# Escorna_Shield_botoneira_2_0B.net
KiCad netlist of a schematic drawn in EAGLE
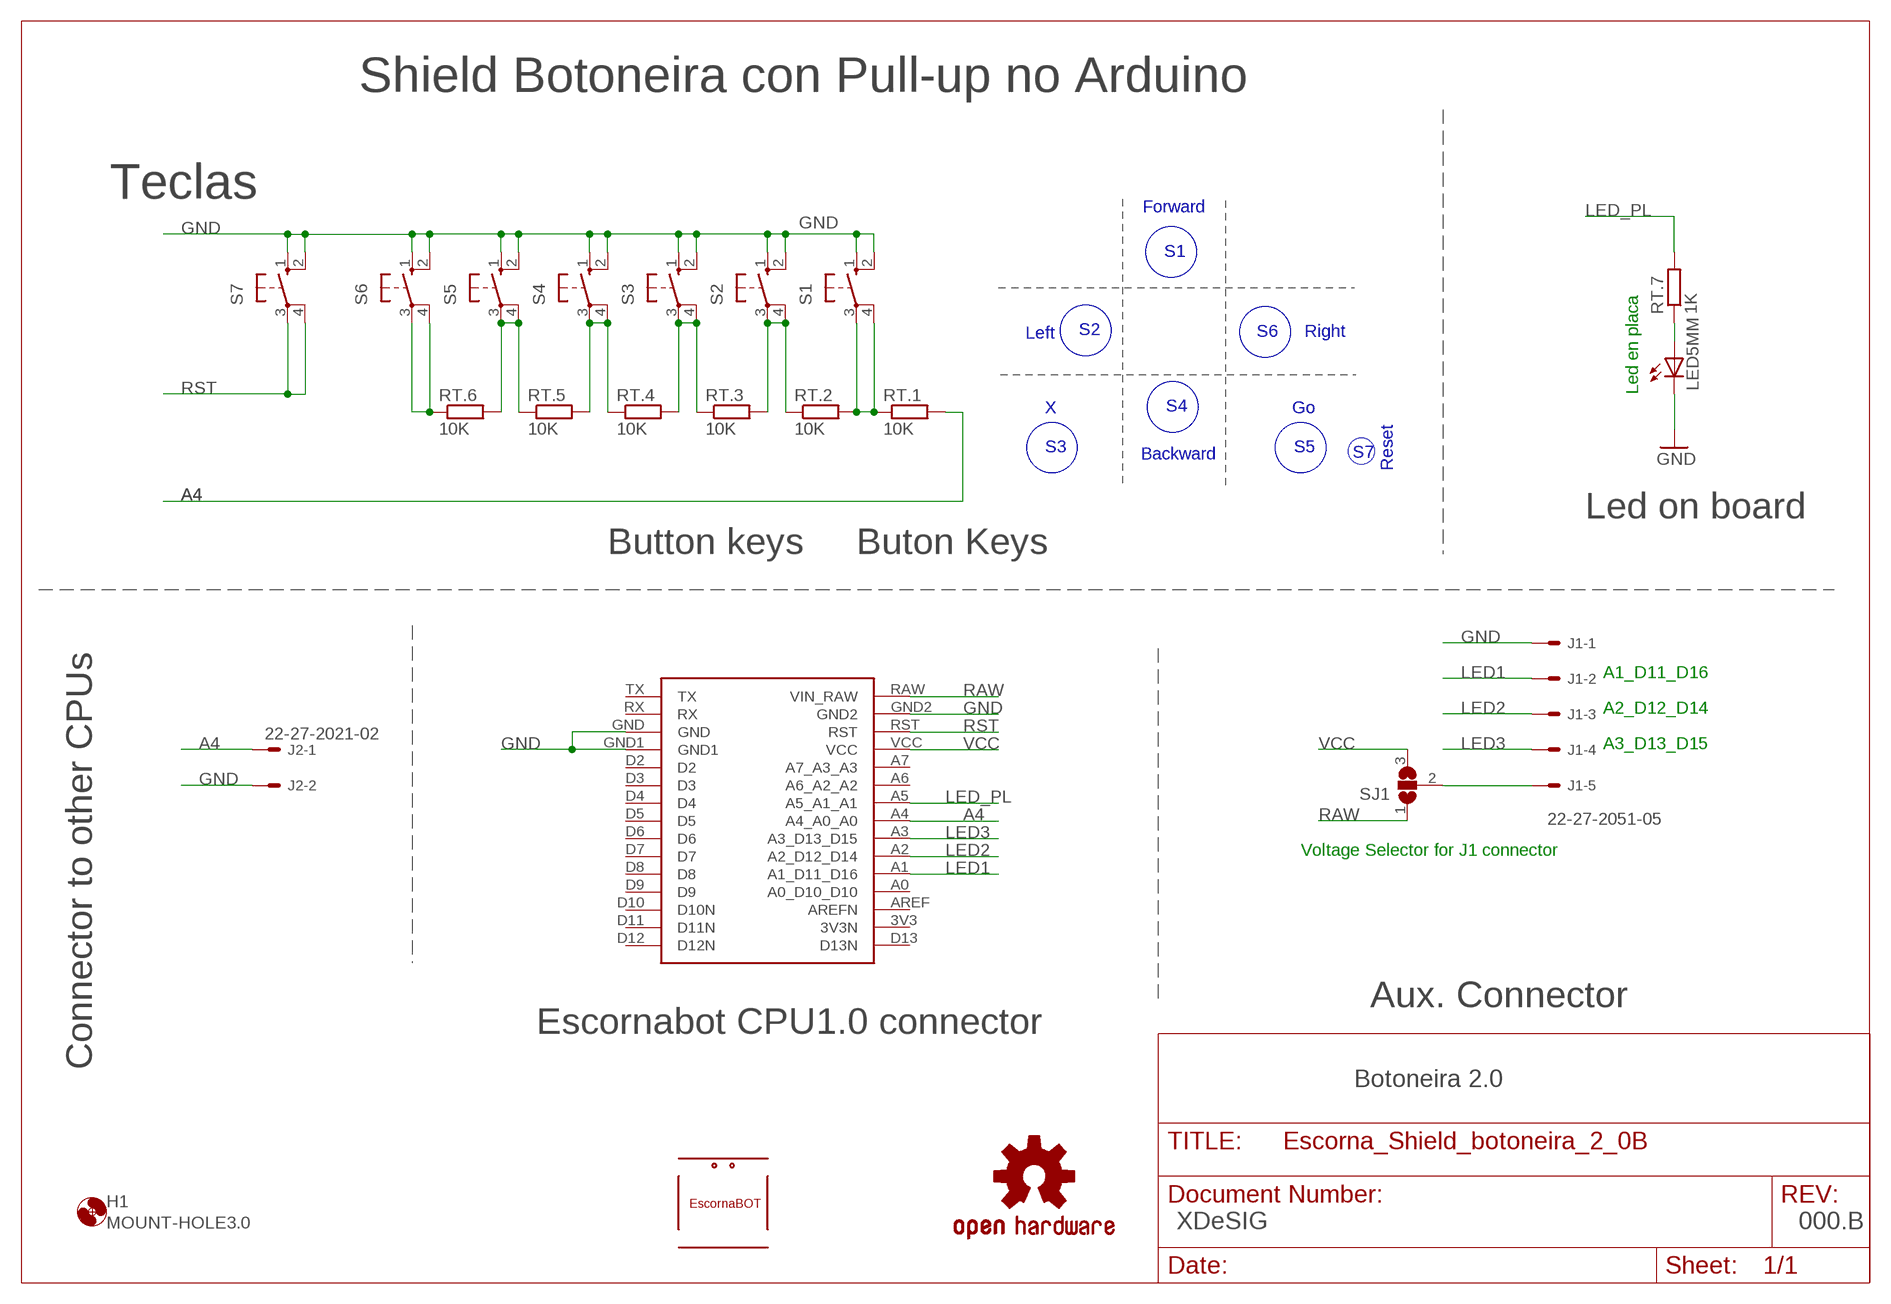
[diagram p0: schematic, sheet 1]

(export (version "E")
  (design (tool "Eeschema 10.0.6"))
  (components
    (comp (ref "ESSH1")
      (value "OUTL_ESCORNASHILED")
      (footprint "eagle-import:OUTL_ESCORNASHIELD")
      (libsource (lib "eagle-import") (part "OUTL_ESCORNASHILED"))
    )
    (comp (ref "H1")
      (value "MOUNT-HOLE3.0")
      (footprint "eagle-import:3,0")
      (libsource (lib "eagle-import") (part "MOUNT-HOLE3.0"))
    )
    (comp (ref "J1")
      (value "22-27-2051-05")
      (footprint "eagle-import:6410-05")
      (libsource (lib "eagle-import") (part "22-?-0527-2051"))
    )
    (comp (ref "J2")
      (value "22-27-2021-02")
      (footprint "eagle-import:6410-02")
      (libsource (lib "eagle-import") (part "22-?-0227-2021"))
    )
    (comp (ref "LED5MM")
      (value "LED5MM")
      (footprint "eagle-import:LED5MM")
      (libsource (lib "eagle-import") (part "LED5MM"))
    )
    (comp (ref "LOGO2")
      (value "OSHW-LOGOS")
      (footprint "eagle-import:OSHW-LOGO-S")
      (libsource (lib "eagle-import") (part "OSHW-LOGOS"))
    )
    (comp (ref "RT.1")
      (value "10K")
      (footprint "eagle-import:0204_7")
      (libsource (lib "eagle-import") (part "R-EU_0204/7"))
    )
    (comp (ref "RT.2")
      (value "10K")
      (footprint "eagle-import:0204_7")
      (libsource (lib "eagle-import") (part "R-EU_0204/7"))
    )
    (comp (ref "RT.3")
      (value "10K")
      (footprint "eagle-import:0204_7")
      (libsource (lib "eagle-import") (part "R-EU_0204/7"))
    )
    (comp (ref "RT.4")
      (value "10K")
      (footprint "eagle-import:0204_7")
      (libsource (lib "eagle-import") (part "R-EU_0204/7"))
    )
    (comp (ref "RT.5")
      (value "10K")
      (footprint "eagle-import:0204_7")
      (libsource (lib "eagle-import") (part "R-EU_0204/7"))
    )
    (comp (ref "RT.6")
      (value "10K")
      (footprint "eagle-import:0204_7")
      (libsource (lib "eagle-import") (part "R-EU_0204/7"))
    )
    (comp (ref "RT.7")
      (value "1K")
      (footprint "eagle-import:0204_7")
      (libsource (lib "eagle-import") (part "R-EU_0204/7"))
    )
    (comp (ref "S1")
      (value "B3F-40XX")
      (footprint "eagle-import:B3F40XX_NH")
      (libsource (lib "eagle-import") (part "40-XX"))
    )
    (comp (ref "S2")
      (value "B3F-40XX")
      (footprint "eagle-import:B3F40XX_NH")
      (libsource (lib "eagle-import") (part "40-XX"))
    )
    (comp (ref "S3")
      (value "B3F-40XX")
      (footprint "eagle-import:B3F40XX_NH")
      (libsource (lib "eagle-import") (part "40-XX"))
    )
    (comp (ref "S4")
      (value "B3F-40XX")
      (footprint "eagle-import:B3F40XX_NH")
      (libsource (lib "eagle-import") (part "40-XX"))
    )
    (comp (ref "S5")
      (value "B3F-40XX")
      (footprint "eagle-import:B3F40XX_NH")
      (libsource (lib "eagle-import") (part "40-XX"))
    )
    (comp (ref "S6")
      (value "B3F-40XX")
      (footprint "eagle-import:B3F40XX_NH")
      (libsource (lib "eagle-import") (part "40-XX"))
    )
    (comp (ref "S7")
      (value "10-XX")
      (footprint "eagle-import:B3F-10XX")
      (fields (field (name "MPN") "B3F-1000"))
      (libsource (lib "eagle-import") (part "10-XX"))
    )
    (comp (ref "SJ1")
      (value "SOLDERJUMPER_2WAY")
      (footprint "eagle-import:SJ_2")
      (libsource (lib "eagle-import") (part "SOLDERJUMPER_2WAY"))
    )
    (comp (ref "U$1")
      (value "ESCORNABOT")
      (footprint "eagle-import:ESCORNA_PEQUE")
      (libsource (lib "eagle-import") (part "ESCORNABOT"))
    )
  )
  (nets
    (net (code "1") (name "/A4") (class "Default")
      (node (ref "ESSH1") (pin "A4") (pinfunction "A4_A0_A0_A4") (pintype "bidirectional"))
      (node (ref "J2") (pin "1") (pinfunction "S_1") (pintype "passive"))
      (node (ref "RT.1") (pin "2") (pinfunction "2_2") (pintype "passive"))
    )
    (net (code "2") (name "/LED1") (class "Default")
      (node (ref "ESSH1") (pin "A1") (pinfunction "A1_D11_D16_A1") (pintype "bidirectional"))
      (node (ref "J1") (pin "2") (pinfunction "S_2") (pintype "passive"))
    )
    (net (code "3") (name "/LED2") (class "Default")
      (node (ref "ESSH1") (pin "A2") (pinfunction "A2_D12_D14_A2") (pintype "bidirectional"))
      (node (ref "J1") (pin "3") (pinfunction "S_3") (pintype "passive"))
    )
    (net (code "4") (name "/LED3") (class "Default")
      (node (ref "ESSH1") (pin "A3") (pinfunction "A3_D13_D15_A3") (pintype "bidirectional"))
      (node (ref "J1") (pin "4") (pinfunction "S_4") (pintype "passive"))
    )
    (net (code "5") (name "/LED_PL") (class "Default")
      (node (ref "ESSH1") (pin "A5") (pinfunction "A5_A1_A1_A5") (pintype "bidirectional"))
      (node (ref "RT.7") (pin "2") (pinfunction "2_2") (pintype "passive"))
    )
    (net (code "6") (name "/RAW") (class "Default")
      (node (ref "ESSH1") (pin "RAW") (pinfunction "VIN_RAW_RAW") (pintype "bidirectional"))
      (node (ref "SJ1") (pin "1") (pinfunction "1_1") (pintype "passive"))
    )
    (net (code "7") (name "/RST") (class "Default")
      (node (ref "ESSH1") (pin "RST") (pinfunction "RST_RST") (pintype "bidirectional"))
      (node (ref "S7") (pin "3") (pinfunction "P_3") (pintype "passive"))
      (node (ref "S7") (pin "4") (pinfunction "P1_4") (pintype "passive"))
    )
    (net (code "8") (name "/VCC") (class "Default")
      (node (ref "ESSH1") (pin "VCC") (pinfunction "VCC_VCC") (pintype "bidirectional"))
      (node (ref "SJ1") (pin "3") (pinfunction "3_3") (pintype "passive"))
    )
    (net (code "9") (name "GND") (class "Default")
      (node (ref "ESSH1") (pin "GND") (pinfunction "GND_GND") (pintype "bidirectional"))
      (node (ref "ESSH1") (pin "GND1") (pinfunction "GND1_GND1") (pintype "bidirectional"))
      (node (ref "ESSH1") (pin "GND2") (pinfunction "GND2_GND2") (pintype "bidirectional"))
      (node (ref "J1") (pin "1") (pinfunction "S_1") (pintype "passive"))
      (node (ref "J2") (pin "2") (pinfunction "S_2") (pintype "passive"))
      (node (ref "LED5MM") (pin "K") (pinfunction "C_K") (pintype "passive"))
      (node (ref "S1") (pin "1") (pinfunction "S_1") (pintype "passive"))
      (node (ref "S1") (pin "2") (pinfunction "S1_2") (pintype "passive"))
      (node (ref "S2") (pin "1") (pinfunction "S_1") (pintype "passive"))
      (node (ref "S2") (pin "2") (pinfunction "S1_2") (pintype "passive"))
      (node (ref "S3") (pin "1") (pinfunction "S_1") (pintype "passive"))
      (node (ref "S3") (pin "2") (pinfunction "S1_2") (pintype "passive"))
      (node (ref "S4") (pin "1") (pinfunction "S_1") (pintype "passive"))
      (node (ref "S4") (pin "2") (pinfunction "S1_2") (pintype "passive"))
      (node (ref "S5") (pin "1") (pinfunction "S_1") (pintype "passive"))
      (node (ref "S5") (pin "2") (pinfunction "S1_2") (pintype "passive"))
      (node (ref "S6") (pin "1") (pinfunction "S_1") (pintype "passive"))
      (node (ref "S6") (pin "2") (pinfunction "S1_2") (pintype "passive"))
      (node (ref "S7") (pin "1") (pinfunction "S_1") (pintype "passive"))
      (node (ref "S7") (pin "2") (pinfunction "S1_2") (pintype "passive"))
    )
    (net (code "10") (name "Net-(J1E-S)") (class "Default")
      (node (ref "J1") (pin "5") (pinfunction "S_5") (pintype "passive"))
      (node (ref "SJ1") (pin "2") (pinfunction "2_2") (pintype "passive"))
    )
    (net (code "11") (name "Net-(LED5MM-PadA)") (class "Default")
      (node (ref "LED5MM") (pin "A") (pinfunction "A_A") (pintype "passive"))
      (node (ref "RT.7") (pin "1") (pinfunction "1_1") (pintype "passive"))
    )
    (net (code "12") (name "Net-(S1-P)") (class "Default")
      (node (ref "RT.1") (pin "1") (pinfunction "1_1") (pintype "passive"))
      (node (ref "RT.2") (pin "2") (pinfunction "2_2") (pintype "passive"))
      (node (ref "S1") (pin "3") (pinfunction "P_3") (pintype "passive"))
      (node (ref "S1") (pin "4") (pinfunction "P1_4") (pintype "passive"))
    )
    (net (code "13") (name "Net-(S2-P)") (class "Default")
      (node (ref "RT.2") (pin "1") (pinfunction "1_1") (pintype "passive"))
      (node (ref "RT.3") (pin "2") (pinfunction "2_2") (pintype "passive"))
      (node (ref "S2") (pin "3") (pinfunction "P_3") (pintype "passive"))
      (node (ref "S2") (pin "4") (pinfunction "P1_4") (pintype "passive"))
    )
    (net (code "14") (name "Net-(S3-P)") (class "Default")
      (node (ref "RT.3") (pin "1") (pinfunction "1_1") (pintype "passive"))
      (node (ref "RT.4") (pin "2") (pinfunction "2_2") (pintype "passive"))
      (node (ref "S3") (pin "3") (pinfunction "P_3") (pintype "passive"))
      (node (ref "S3") (pin "4") (pinfunction "P1_4") (pintype "passive"))
    )
    (net (code "15") (name "Net-(S4-P)") (class "Default")
      (node (ref "RT.4") (pin "1") (pinfunction "1_1") (pintype "passive"))
      (node (ref "RT.5") (pin "2") (pinfunction "2_2") (pintype "passive"))
      (node (ref "S4") (pin "3") (pinfunction "P_3") (pintype "passive"))
      (node (ref "S4") (pin "4") (pinfunction "P1_4") (pintype "passive"))
    )
    (net (code "16") (name "Net-(S5-P)") (class "Default")
      (node (ref "RT.5") (pin "1") (pinfunction "1_1") (pintype "passive"))
      (node (ref "RT.6") (pin "2") (pinfunction "2_2") (pintype "passive"))
      (node (ref "S5") (pin "3") (pinfunction "P_3") (pintype "passive"))
      (node (ref "S5") (pin "4") (pinfunction "P1_4") (pintype "passive"))
    )
    (net (code "17") (name "Net-(S6-P)") (class "Default")
      (node (ref "RT.6") (pin "1") (pinfunction "1_1") (pintype "passive"))
      (node (ref "S6") (pin "3") (pinfunction "P_3") (pintype "passive"))
      (node (ref "S6") (pin "4") (pinfunction "P1_4") (pintype "passive"))
    )
    (net (code "18") (name "unconnected-(ESSH1-3V3N-Pad3V3)") (class "Default")
      (node (ref "ESSH1") (pin "3V3") (pinfunction "3V3N_3V3") (pintype "bidirectional"))
    )
    (net (code "19") (name "unconnected-(ESSH1-A0_D10_D10-PadA0)") (class "Default")
      (node (ref "ESSH1") (pin "A0") (pinfunction "A0_D10_D10_A0") (pintype "bidirectional"))
    )
    (net (code "20") (name "unconnected-(ESSH1-A6_A2_A2-PadA6)") (class "Default")
      (node (ref "ESSH1") (pin "A6") (pinfunction "A6_A2_A2_A6") (pintype "bidirectional"))
    )
    (net (code "21") (name "unconnected-(ESSH1-A7_A3_A3-PadA7)") (class "Default")
      (node (ref "ESSH1") (pin "A7") (pinfunction "A7_A3_A3_A7") (pintype "bidirectional"))
    )
    (net (code "22") (name "unconnected-(ESSH1-AREFN-PadAREF)") (class "Default")
      (node (ref "ESSH1") (pin "AREF") (pinfunction "AREFN_AREF") (pintype "bidirectional"))
    )
    (net (code "23") (name "unconnected-(ESSH1-D10N-PadD10)") (class "Default")
      (node (ref "ESSH1") (pin "D10") (pinfunction "D10N_D10") (pintype "bidirectional"))
    )
    (net (code "24") (name "unconnected-(ESSH1-D11N-PadD11)") (class "Default")
      (node (ref "ESSH1") (pin "D11") (pinfunction "D11N_D11") (pintype "bidirectional"))
    )
    (net (code "25") (name "unconnected-(ESSH1-D12N-PadD12)") (class "Default")
      (node (ref "ESSH1") (pin "D12") (pinfunction "D12N_D12") (pintype "bidirectional"))
    )
    (net (code "26") (name "unconnected-(ESSH1-D13N-PadD13)") (class "Default")
      (node (ref "ESSH1") (pin "D13") (pinfunction "D13N_D13") (pintype "bidirectional"))
    )
    (net (code "27") (name "unconnected-(ESSH1-PadD2)") (class "Default")
      (node (ref "ESSH1") (pin "D2") (pinfunction "D2_D2") (pintype "bidirectional"))
    )
    (net (code "28") (name "unconnected-(ESSH1-PadD3)") (class "Default")
      (node (ref "ESSH1") (pin "D3") (pinfunction "D3_D3") (pintype "bidirectional"))
    )
    (net (code "29") (name "unconnected-(ESSH1-PadD4)") (class "Default")
      (node (ref "ESSH1") (pin "D4") (pinfunction "D4_D4") (pintype "bidirectional"))
    )
    (net (code "30") (name "unconnected-(ESSH1-PadD5)") (class "Default")
      (node (ref "ESSH1") (pin "D5") (pinfunction "D5_D5") (pintype "bidirectional"))
    )
    (net (code "31") (name "unconnected-(ESSH1-PadD6)") (class "Default")
      (node (ref "ESSH1") (pin "D6") (pinfunction "D6_D6") (pintype "bidirectional"))
    )
    (net (code "32") (name "unconnected-(ESSH1-PadD7)") (class "Default")
      (node (ref "ESSH1") (pin "D7") (pinfunction "D7_D7") (pintype "bidirectional"))
    )
    (net (code "33") (name "unconnected-(ESSH1-PadD8)") (class "Default")
      (node (ref "ESSH1") (pin "D8") (pinfunction "D8_D8") (pintype "bidirectional"))
    )
    (net (code "34") (name "unconnected-(ESSH1-PadD9)") (class "Default")
      (node (ref "ESSH1") (pin "D9") (pinfunction "D9_D9") (pintype "bidirectional"))
    )
    (net (code "35") (name "unconnected-(ESSH1-PadRX)") (class "Default")
      (node (ref "ESSH1") (pin "RX") (pinfunction "RX_RX") (pintype "bidirectional"))
    )
    (net (code "36") (name "unconnected-(ESSH1-PadTX)") (class "Default")
      (node (ref "ESSH1") (pin "TX") (pinfunction "TX_TX") (pintype "bidirectional"))
    )
  )
)
